# SCH_usb-hub_2024-07-20.net
KiCad netlist of a schematic drawn in EasyEDA
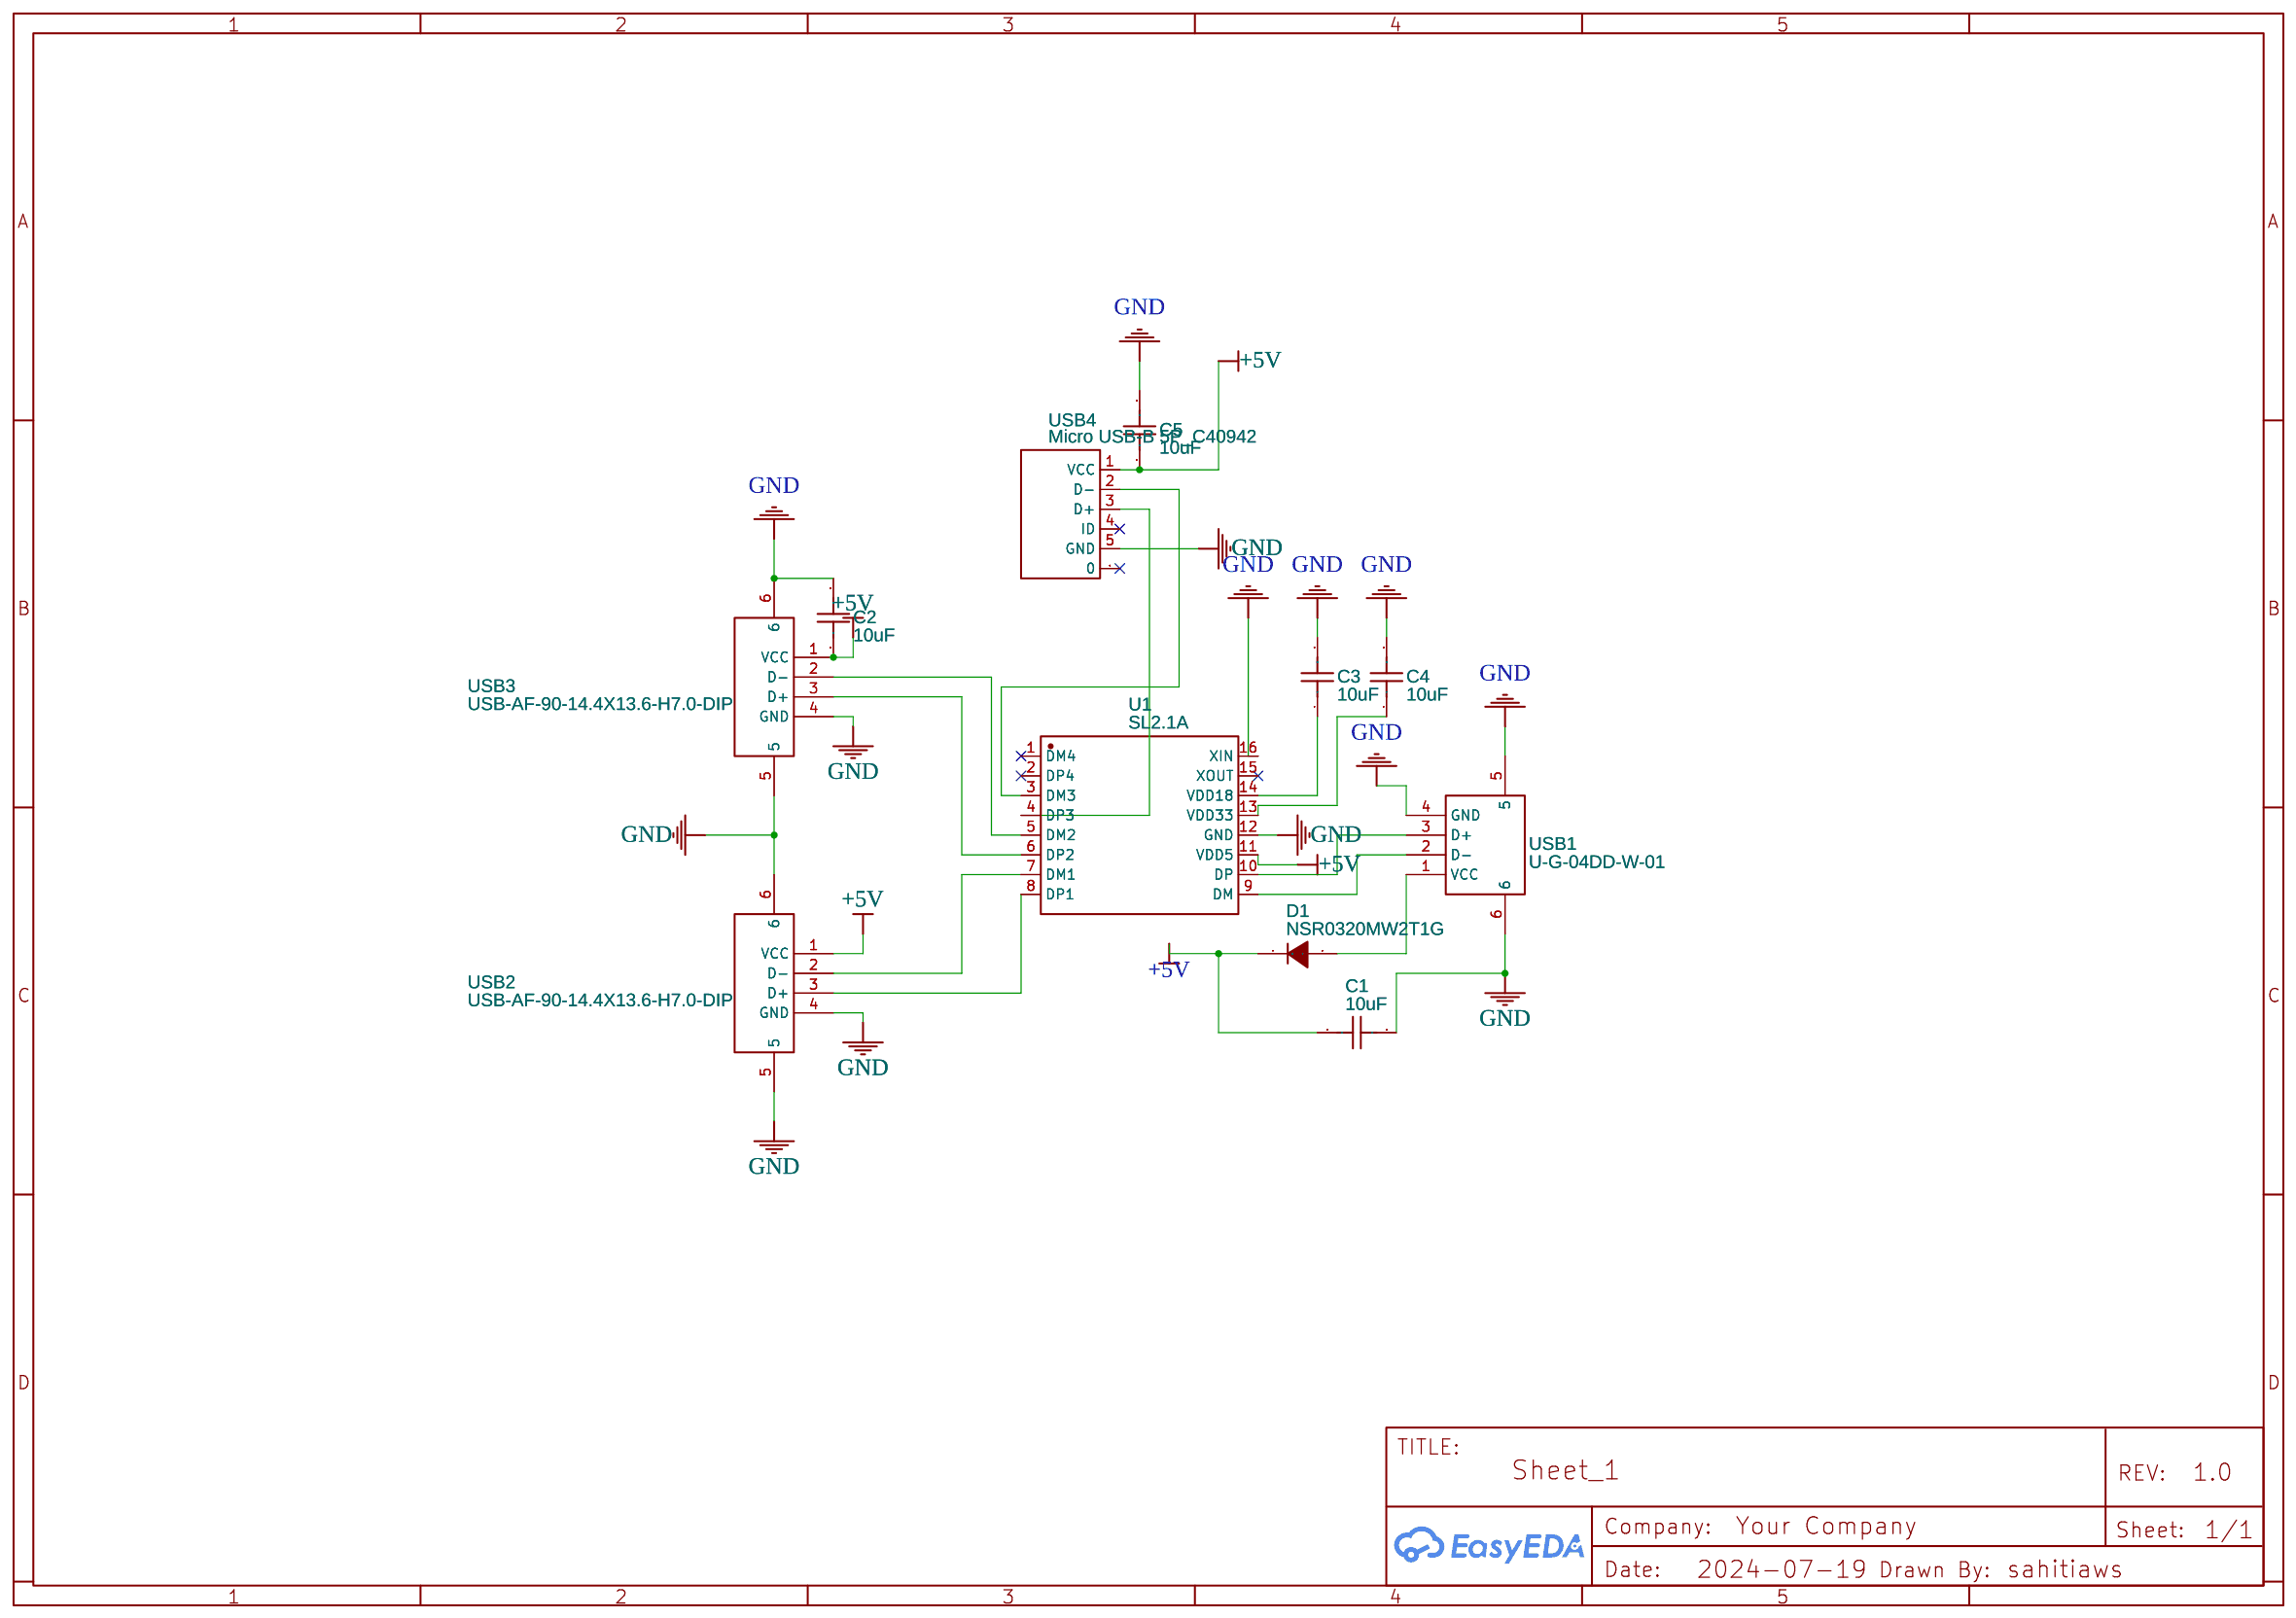
[diagram p0: schematic sheet]

(export (version "E")
  (design (tool "Eeschema 10.0.6"))
  (components
    (comp (ref "C1")
      (value "10uF")
      (fields
        (field (name "Manufacturer Part") "CL10A106KP8NNNC")
        (field (name "Manufacturer") "SAMSUNG(三星)")
      )
      (libsource (lib "") (part "CL10A106KP8NNNC"))
    )
    (comp (ref "C2")
      (value "10uF")
      (fields
        (field (name "Manufacturer Part") "CL10A106KP8NNNC")
        (field (name "Manufacturer") "SAMSUNG(三星)")
      )
      (libsource (lib "") (part "CL10A106KP8NNNC_1"))
    )
    (comp (ref "C3")
      (value "10uF")
      (fields
        (field (name "Manufacturer Part") "CL10A106KP8NNNC")
        (field (name "Manufacturer") "SAMSUNG(三星)")
      )
      (libsource (lib "") (part "CL10A106KP8NNNC_1"))
    )
    (comp (ref "C4")
      (value "10uF")
      (fields
        (field (name "Manufacturer Part") "CL10A106KP8NNNC")
        (field (name "Manufacturer") "SAMSUNG(三星)")
      )
      (libsource (lib "") (part "CL10A106KP8NNNC_1"))
    )
    (comp (ref "C5")
      (value "10uF")
      (fields
        (field (name "Manufacturer Part") "CL10A106KP8NNNC")
        (field (name "Manufacturer") "SAMSUNG(三星)")
      )
      (libsource (lib "") (part "CL10A106KP8NNNC_1"))
    )
    (comp (ref "D1")
      (value "NSR0320MW2T1G")
      (fields (field (name "Manufacturer") "onsemi(安森美)"))
      (libsource (lib "") (part "NSR0320MW2T1G"))
    )
    (comp (ref "U1")
      (value "SL2.1A")
      (fields (field (name "Manufacturer") "CoreChips(和芯润德)"))
      (libsource (lib "") (part "SL2.1A"))
    )
    (comp (ref "USB1")
      (value "U-G-04DD-W-01")
      (fields (field (name "Manufacturer Part") "U-G-O4DD-W-1") (field (name "Manufacturer") "韩国韩荣"))
      (libsource (lib "") (part "U-G-04DD-W-01"))
    )
    (comp (ref "USB2")
      (value "USB-AF-90-14.4X13.6-H7.0-DIP")
      (fields (field (name "Manufacturer Part") "903-131A1011D10100") (field (name "Manufacturer") "精拓金"))
      (libsource (lib "") (part "USB-AF-90-14.4X13.6-H7.0-DIP"))
    )
    (comp (ref "USB3")
      (value "USB-AF-90-14.4X13.6-H7.0-DIP")
      (fields (field (name "Manufacturer Part") "903-131A1011D10100") (field (name "Manufacturer") "精拓金"))
      (libsource (lib "") (part "USB-AF-90-14.4X13.6-H7.0-DIP"))
    )
    (comp (ref "USB4")
      (value "Micro USB-B 5P_C40942")
      (fields (field (name "Manufacturer Part") "920-D62A2021S10100") (field (name "Manufacturer") "精拓金"))
      (libsource (lib "") (part "Micro USB-B 5P_C40942"))
    )
  )
  (nets
    (net (code "1") (name "+5V") (class "Default")
      (node (ref "C1") (pin "1") (pinfunction "1_1") (pintype "unspecified"))
      (node (ref "C2") (pin "1") (pinfunction "1_1") (pintype "unspecified"))
      (node (ref "C5") (pin "1") (pinfunction "1_1") (pintype "unspecified"))
      (node (ref "D1") (pin "1") (pinfunction "C_1") (pintype "unspecified"))
      (node (ref "U1") (pin "11") (pinfunction "VDD5_11") (pintype "unspecified"))
      (node (ref "USB2") (pin "1") (pinfunction "VCC_1") (pintype "unspecified"))
      (node (ref "USB3") (pin "1") (pinfunction "VCC_1") (pintype "unspecified"))
      (node (ref "USB4") (pin "1") (pinfunction "VCC_1") (pintype "input"))
    )
    (net (code "2") (name "GND") (class "Default")
      (node (ref "C1") (pin "2") (pinfunction "2_2") (pintype "unspecified"))
      (node (ref "C2") (pin "2") (pinfunction "2_2") (pintype "unspecified"))
      (node (ref "C3") (pin "2") (pinfunction "2_2") (pintype "unspecified"))
      (node (ref "C4") (pin "2") (pinfunction "2_2") (pintype "unspecified"))
      (node (ref "C5") (pin "2") (pinfunction "2_2") (pintype "unspecified"))
      (node (ref "U1") (pin "12") (pinfunction "GND_12") (pintype "unspecified"))
      (node (ref "U1") (pin "16") (pinfunction "XIN_16") (pintype "unspecified"))
      (node (ref "USB1") (pin "4") (pinfunction "GND_4") (pintype "unspecified"))
      (node (ref "USB1") (pin "5") (pinfunction "5_5") (pintype "unspecified"))
      (node (ref "USB1") (pin "6") (pinfunction "6_6") (pintype "unspecified"))
      (node (ref "USB2") (pin "4") (pinfunction "GND_4") (pintype "unspecified"))
      (node (ref "USB2") (pin "5") (pinfunction "5_5") (pintype "unspecified"))
      (node (ref "USB2") (pin "6") (pinfunction "6_6") (pintype "unspecified"))
      (node (ref "USB3") (pin "4") (pinfunction "GND_4") (pintype "unspecified"))
      (node (ref "USB3") (pin "5") (pinfunction "5_5") (pintype "unspecified"))
      (node (ref "USB3") (pin "6") (pinfunction "6_6") (pintype "unspecified"))
      (node (ref "USB4") (pin "5") (pinfunction "GND_5") (pintype "input"))
    )
    (net (code "3") (name "Net-(D1-A)") (class "Default")
      (node (ref "D1") (pin "2") (pinfunction "A_2") (pintype "unspecified"))
      (node (ref "USB1") (pin "1") (pinfunction "VCC_1") (pintype "unspecified"))
    )
    (net (code "4") (name "Net-(U1-DM)") (class "Default")
      (node (ref "U1") (pin "9") (pinfunction "DM_9") (pintype "unspecified"))
      (node (ref "USB1") (pin "2") (pinfunction "D-_2") (pintype "unspecified"))
    )
    (net (code "5") (name "Net-(U1-DM1)") (class "Default")
      (node (ref "U1") (pin "7") (pinfunction "DM1_7") (pintype "unspecified"))
      (node (ref "USB2") (pin "2") (pinfunction "D-_2") (pintype "unspecified"))
    )
    (net (code "6") (name "Net-(U1-DM2)") (class "Default")
      (node (ref "U1") (pin "5") (pinfunction "DM2_5") (pintype "unspecified"))
      (node (ref "USB3") (pin "2") (pinfunction "D-_2") (pintype "unspecified"))
    )
    (net (code "7") (name "Net-(U1-DM3)") (class "Default")
      (node (ref "U1") (pin "3") (pinfunction "DM3_3") (pintype "unspecified"))
      (node (ref "USB4") (pin "2") (pinfunction "D-_2") (pintype "input"))
    )
    (net (code "8") (name "Net-(U1-DP)") (class "Default")
      (node (ref "U1") (pin "10") (pinfunction "DP_10") (pintype "unspecified"))
      (node (ref "USB1") (pin "3") (pinfunction "D+_3") (pintype "unspecified"))
    )
    (net (code "9") (name "Net-(U1-DP1)") (class "Default")
      (node (ref "U1") (pin "8") (pinfunction "DP1_8") (pintype "unspecified"))
      (node (ref "USB2") (pin "3") (pinfunction "D+_3") (pintype "unspecified"))
    )
    (net (code "10") (name "Net-(U1-DP2)") (class "Default")
      (node (ref "U1") (pin "6") (pinfunction "DP2_6") (pintype "unspecified"))
      (node (ref "USB3") (pin "3") (pinfunction "D+_3") (pintype "unspecified"))
    )
    (net (code "11") (name "Net-(U1-DP3)") (class "Default")
      (node (ref "U1") (pin "4") (pinfunction "DP3_4") (pintype "unspecified"))
      (node (ref "USB4") (pin "3") (pinfunction "D+_3") (pintype "input"))
    )
    (net (code "12") (name "Net-(U1-VDD18)") (class "Default")
      (node (ref "C3") (pin "1") (pinfunction "1_1") (pintype "unspecified"))
      (node (ref "U1") (pin "14") (pinfunction "VDD18_14") (pintype "unspecified"))
    )
    (net (code "13") (name "Net-(U1-VDD33)") (class "Default")
      (node (ref "C4") (pin "1") (pinfunction "1_1") (pintype "unspecified"))
      (node (ref "U1") (pin "13") (pinfunction "VDD33_13") (pintype "unspecified"))
    )
    (net (code "14") (name "unconnected-(U1-DM4-Pad1)") (class "Default")
      (node (ref "U1") (pin "1") (pinfunction "DM4_1") (pintype "unspecified+no_connect"))
    )
    (net (code "15") (name "unconnected-(U1-DP4-Pad2)") (class "Default")
      (node (ref "U1") (pin "2") (pinfunction "DP4_2") (pintype "unspecified+no_connect"))
    )
    (net (code "16") (name "unconnected-(U1-XOUT-Pad15)") (class "Default")
      (node (ref "U1") (pin "15") (pinfunction "XOUT_15") (pintype "unspecified+no_connect"))
    )
    (net (code "17") (name "unconnected-(USB4-ID-Pad4)") (class "Default")
      (node (ref "USB4") (pin "4") (pinfunction "ID_4") (pintype "input+no_connect"))
    )
    (net (code "18") (name "unconnected-(USB4-Pad0)") (class "Default")
      (node (ref "USB4") (pin "0") (pinfunction "0_0") (pintype "input+no_connect"))
    )
  )
)
